# RS485Interface.net
KiCad netlist of a schematic drawn in EAGLE
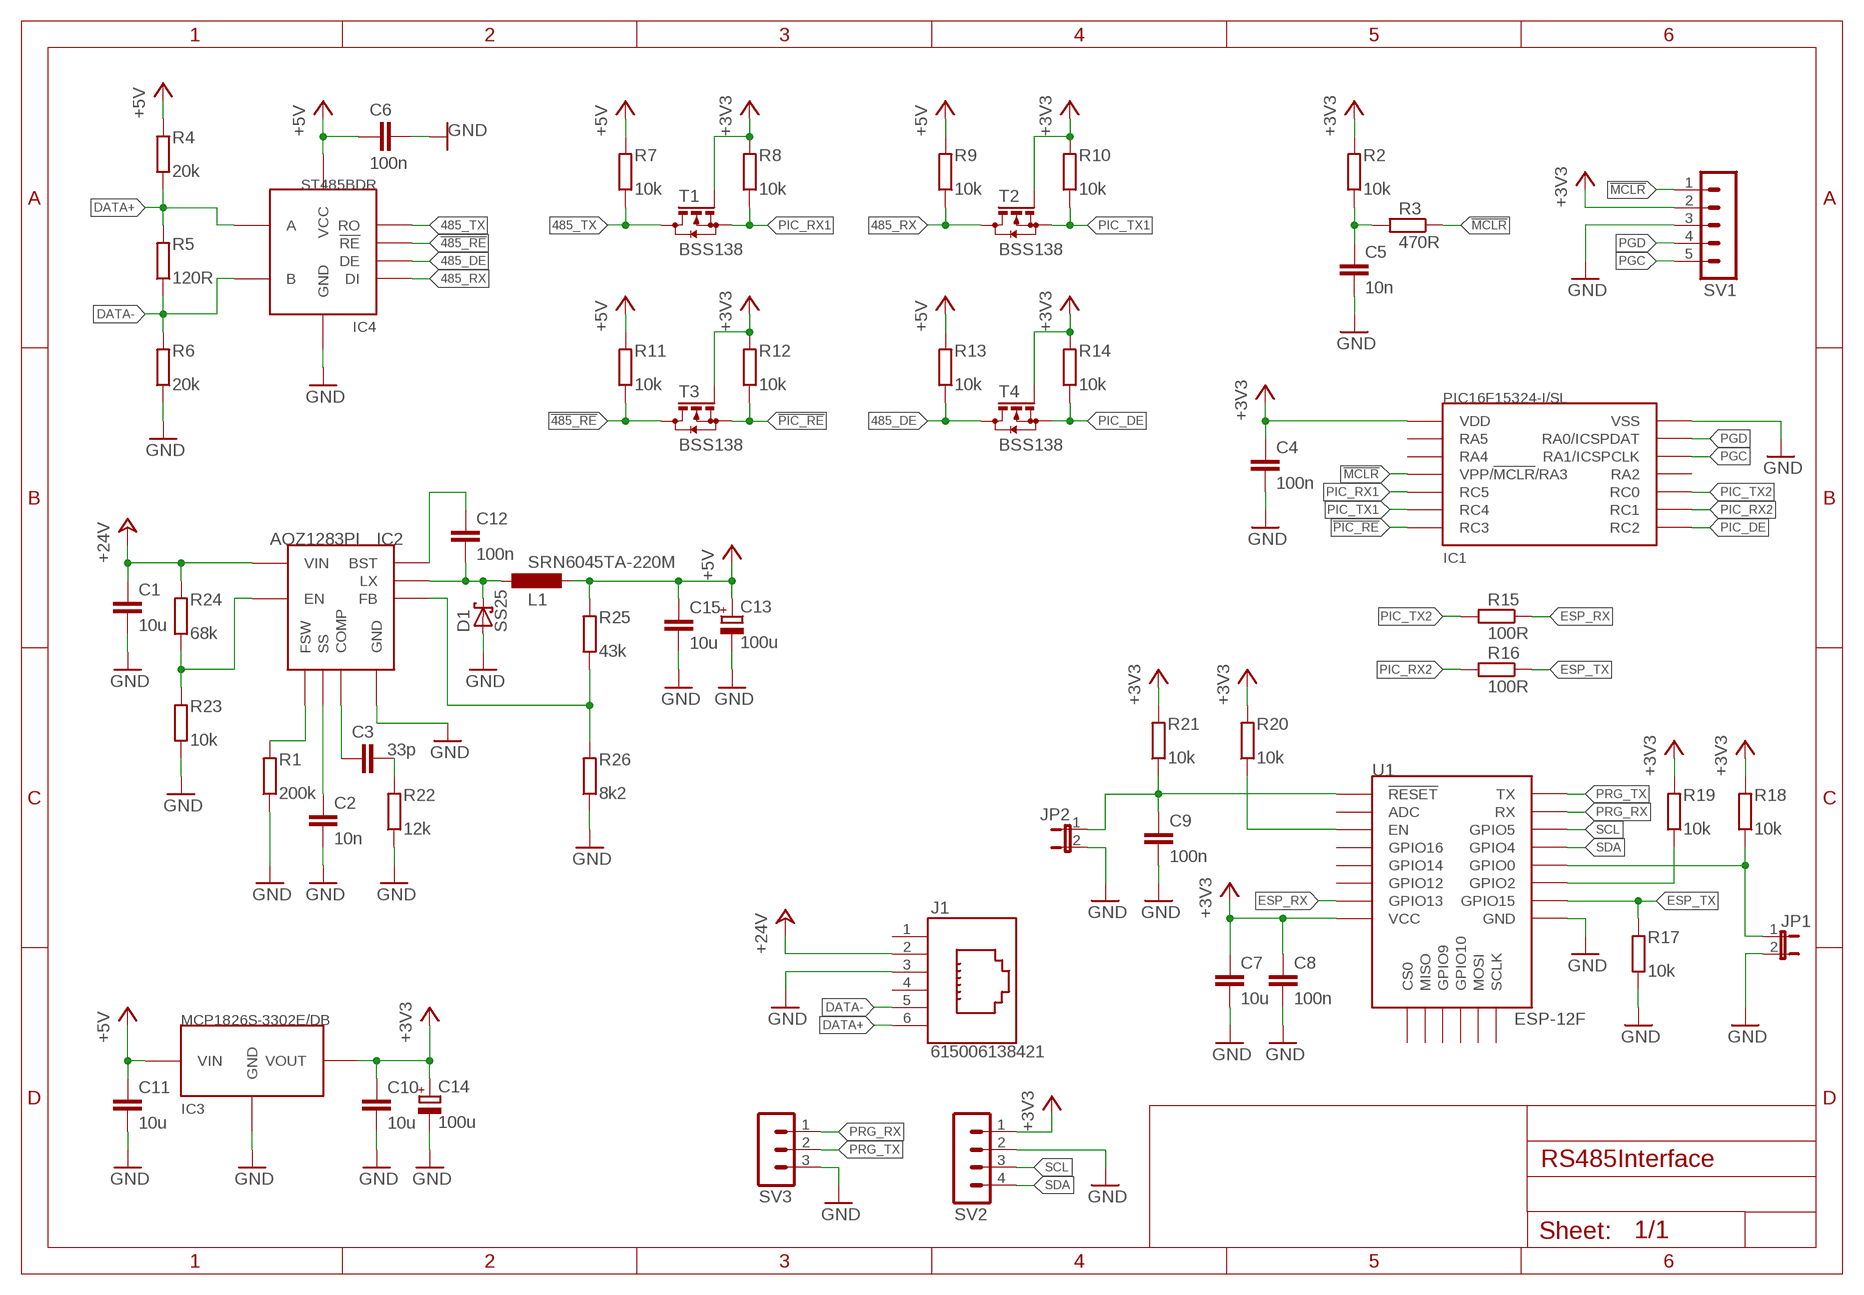
[diagram p0: schematic, sheet 1]

(export (version "E")
  (design (tool "Eeschema 10.0.6"))
  (components
    (comp (ref "C1")
      (value "10u")
      (footprint "eagle-import:C0805")
      (libsource (lib "eagle-import") (part "C-EUC0805"))
    )
    (comp (ref "C2")
      (value "10n")
      (footprint "eagle-import:C0805")
      (libsource (lib "eagle-import") (part "C-EUC0805"))
    )
    (comp (ref "C3")
      (value "33p")
      (footprint "eagle-import:C0805")
      (libsource (lib "eagle-import") (part "C-EUC0805"))
    )
    (comp (ref "C4")
      (value "100n")
      (footprint "eagle-import:C0805")
      (libsource (lib "eagle-import") (part "C-EUC0805"))
    )
    (comp (ref "C5")
      (value "10n")
      (footprint "eagle-import:C0805")
      (libsource (lib "eagle-import") (part "C-EUC0805"))
    )
    (comp (ref "C6")
      (value "100n")
      (footprint "eagle-import:C0805")
      (libsource (lib "eagle-import") (part "C-EUC0805"))
    )
    (comp (ref "C7")
      (value "10u")
      (footprint "eagle-import:C0805")
      (libsource (lib "eagle-import") (part "C-EUC0805"))
    )
    (comp (ref "C8")
      (value "100n")
      (footprint "eagle-import:C0805")
      (libsource (lib "eagle-import") (part "C-EUC0805"))
    )
    (comp (ref "C9")
      (value "100n")
      (footprint "eagle-import:C0805")
      (libsource (lib "eagle-import") (part "C-EUC0805"))
    )
    (comp (ref "C10")
      (value "10u")
      (footprint "eagle-import:C0805")
      (libsource (lib "eagle-import") (part "C-EUC0805"))
    )
    (comp (ref "C11")
      (value "10u")
      (footprint "eagle-import:C0805")
      (libsource (lib "eagle-import") (part "C-EUC0805"))
    )
    (comp (ref "C12")
      (value "100n")
      (footprint "eagle-import:C0805")
      (libsource (lib "eagle-import") (part "C-EUC0805"))
    )
    (comp (ref "C13")
      (value "100u")
      (footprint "eagle-import:UCL6.3")
      (libsource (lib "eagle-import") (part "UCL"))
    )
    (comp (ref "C14")
      (value "100u")
      (footprint "eagle-import:UCL6.3")
      (libsource (lib "eagle-import") (part "UCL"))
    )
    (comp (ref "C15")
      (value "10u")
      (footprint "eagle-import:C0805")
      (libsource (lib "eagle-import") (part "C-EUC0805"))
    )
    (comp (ref "D1")
      (value "SS25")
      (footprint "eagle-import:DO-214AA")
      (libsource (lib "eagle-import") (part "SS25"))
    )
    (comp (ref "IC1")
      (value "PIC16F15324-I/SL")
      (footprint "eagle-import:SOIC14")
      (libsource (lib "eagle-import") (part "PIC16F15324-I/SL"))
    )
    (comp (ref "IC2")
      (value "AOZ1283PI")
      (footprint "eagle-import:SO8+PAD")
      (libsource (lib "eagle-import") (part "AOZ1283PI"))
    )
    (comp (ref "IC3")
      (value "MCP1826S-3302E/DB")
      (footprint "eagle-import:SOT-223-3")
      (libsource (lib "eagle-import") (part "MCP1826S-3302E/DB"))
    )
    (comp (ref "IC4")
      (value "ST485BDR")
      (footprint "eagle-import:SOIC8")
      (libsource (lib "eagle-import") (part "ST485BDR"))
    )
    (comp (ref "J1")
      (value "615006138421")
      (footprint "eagle-import:615006138421")
      (libsource (lib "eagle-import") (part "615006138421"))
    )
    (comp (ref "JP1")
      (value "JP1E")
      (footprint "eagle-import:JP1")
      (libsource (lib "eagle-import") (part "JP1E"))
    )
    (comp (ref "JP2")
      (value "JP1E")
      (footprint "eagle-import:JP1")
      (libsource (lib "eagle-import") (part "JP1E"))
    )
    (comp (ref "L1")
      (value "SRN6045TA-220M")
      (footprint "eagle-import:SRN6045TA")
      (libsource (lib "eagle-import") (part "SRN6045TA-220M"))
    )
    (comp (ref "R1")
      (value "200k")
      (footprint "eagle-import:R0805")
      (libsource (lib "eagle-import") (part "R-EU_R0805"))
    )
    (comp (ref "R2")
      (value "10k")
      (footprint "eagle-import:R0805")
      (libsource (lib "eagle-import") (part "R-EU_R0805"))
    )
    (comp (ref "R3")
      (value "470R")
      (footprint "eagle-import:R0805")
      (libsource (lib "eagle-import") (part "R-EU_R0805"))
    )
    (comp (ref "R4")
      (value "20k")
      (footprint "eagle-import:R0805")
      (libsource (lib "eagle-import") (part "R-EU_R0805"))
    )
    (comp (ref "R5")
      (value "120R")
      (footprint "eagle-import:R0805")
      (libsource (lib "eagle-import") (part "R-EU_R0805"))
    )
    (comp (ref "R6")
      (value "20k")
      (footprint "eagle-import:R0805")
      (libsource (lib "eagle-import") (part "R-EU_R0805"))
    )
    (comp (ref "R7")
      (value "10k")
      (footprint "eagle-import:R0805")
      (libsource (lib "eagle-import") (part "R-EU_R0805"))
    )
    (comp (ref "R8")
      (value "10k")
      (footprint "eagle-import:R0805")
      (libsource (lib "eagle-import") (part "R-EU_R0805"))
    )
    (comp (ref "R9")
      (value "10k")
      (footprint "eagle-import:R0805")
      (libsource (lib "eagle-import") (part "R-EU_R0805"))
    )
    (comp (ref "R10")
      (value "10k")
      (footprint "eagle-import:R0805")
      (libsource (lib "eagle-import") (part "R-EU_R0805"))
    )
    (comp (ref "R11")
      (value "10k")
      (footprint "eagle-import:R0805")
      (libsource (lib "eagle-import") (part "R-EU_R0805"))
    )
    (comp (ref "R12")
      (value "10k")
      (footprint "eagle-import:R0805")
      (libsource (lib "eagle-import") (part "R-EU_R0805"))
    )
    (comp (ref "R13")
      (value "10k")
      (footprint "eagle-import:R0805")
      (libsource (lib "eagle-import") (part "R-EU_R0805"))
    )
    (comp (ref "R14")
      (value "10k")
      (footprint "eagle-import:R0805")
      (libsource (lib "eagle-import") (part "R-EU_R0805"))
    )
    (comp (ref "R15")
      (value "100R")
      (footprint "eagle-import:R0805")
      (libsource (lib "eagle-import") (part "R-EU_R0805"))
    )
    (comp (ref "R16")
      (value "100R")
      (footprint "eagle-import:R0805")
      (libsource (lib "eagle-import") (part "R-EU_R0805"))
    )
    (comp (ref "R17")
      (value "10k")
      (footprint "eagle-import:R0805")
      (libsource (lib "eagle-import") (part "R-EU_R0805"))
    )
    (comp (ref "R18")
      (value "10k")
      (footprint "eagle-import:R0805")
      (libsource (lib "eagle-import") (part "R-EU_R0805"))
    )
    (comp (ref "R19")
      (value "10k")
      (footprint "eagle-import:R0805")
      (libsource (lib "eagle-import") (part "R-EU_R0805"))
    )
    (comp (ref "R20")
      (value "10k")
      (footprint "eagle-import:R0805")
      (libsource (lib "eagle-import") (part "R-EU_R0805"))
    )
    (comp (ref "R21")
      (value "10k")
      (footprint "eagle-import:R0805")
      (libsource (lib "eagle-import") (part "R-EU_R0805"))
    )
    (comp (ref "R22")
      (value "12k")
      (footprint "eagle-import:R0805")
      (libsource (lib "eagle-import") (part "R-EU_R0805"))
    )
    (comp (ref "R23")
      (value "10k")
      (footprint "eagle-import:R0805")
      (libsource (lib "eagle-import") (part "R-EU_R0805"))
    )
    (comp (ref "R24")
      (value "68k")
      (footprint "eagle-import:R0805")
      (libsource (lib "eagle-import") (part "R-EU_R0805"))
    )
    (comp (ref "R25")
      (value "43k")
      (footprint "eagle-import:R0805")
      (libsource (lib "eagle-import") (part "R-EU_R0805"))
    )
    (comp (ref "R26")
      (value "8k2")
      (footprint "eagle-import:R0805")
      (libsource (lib "eagle-import") (part "R-EU_R0805"))
    )
    (comp (ref "SV1")
      (value "MA05-1")
      (footprint "eagle-import:MA05-1")
      (libsource (lib "eagle-import") (part "MA05-1"))
    )
    (comp (ref "SV2")
      (value "MA04-1")
      (footprint "eagle-import:MA04-1")
      (libsource (lib "eagle-import") (part "MA04-1"))
    )
    (comp (ref "SV3")
      (value "MA03-1")
      (footprint "eagle-import:MA03-1")
      (libsource (lib "eagle-import") (part "MA03-1"))
    )
    (comp (ref "T1")
      (value "BSS138")
      (footprint "eagle-import:SOT-23")
      (libsource (lib "eagle-import") (part "BSS138"))
    )
    (comp (ref "T2")
      (value "BSS138")
      (footprint "eagle-import:SOT-23")
      (libsource (lib "eagle-import") (part "BSS138"))
    )
    (comp (ref "T3")
      (value "BSS138")
      (footprint "eagle-import:SOT-23")
      (libsource (lib "eagle-import") (part "BSS138"))
    )
    (comp (ref "T4")
      (value "BSS138")
      (footprint "eagle-import:SOT-23")
      (libsource (lib "eagle-import") (part "BSS138"))
    )
    (comp (ref "U1")
      (value "ESP-12F")
      (footprint "eagle-import:ESP12E-SMD")
      (libsource (lib "eagle-import") (part "ESP12ESMD"))
    )
  )
  (nets
    (net (code "1") (name "+3V3") (class "Default")
      (node (ref "C10") (pin "1") (pinfunction "1_1") (pintype "passive"))
      (node (ref "C14") (pin "+") (pinfunction "+_+") (pintype "passive"))
      (node (ref "C4") (pin "1") (pinfunction "1_1") (pintype "passive"))
      (node (ref "C7") (pin "1") (pinfunction "1_1") (pintype "passive"))
      (node (ref "C8") (pin "1") (pinfunction "1_1") (pintype "passive"))
      (node (ref "IC1") (pin "P1") (pinfunction "VDD_P1") (pintype "power_in"))
      (node (ref "IC3") (pin "P3") (pinfunction "VOUT_P3") (pintype "power_in"))
      (node (ref "R10") (pin "2") (pinfunction "2_2") (pintype "passive"))
      (node (ref "R12") (pin "2") (pinfunction "2_2") (pintype "passive"))
      (node (ref "R14") (pin "2") (pinfunction "2_2") (pintype "passive"))
      (node (ref "R18") (pin "2") (pinfunction "2_2") (pintype "passive"))
      (node (ref "R19") (pin "2") (pinfunction "2_2") (pintype "passive"))
      (node (ref "R2") (pin "2") (pinfunction "2_2") (pintype "passive"))
      (node (ref "R20") (pin "2") (pinfunction "2_2") (pintype "passive"))
      (node (ref "R21") (pin "2") (pinfunction "2_2") (pintype "passive"))
      (node (ref "R8") (pin "2") (pinfunction "2_2") (pintype "passive"))
      (node (ref "SV1") (pin "2") (pinfunction "2_2") (pintype "passive"))
      (node (ref "SV2") (pin "1") (pinfunction "1_1") (pintype "passive"))
      (node (ref "T1") (pin "P1") (pinfunction "G_P1") (pintype "passive"))
      (node (ref "T2") (pin "P1") (pinfunction "G_P1") (pintype "passive"))
      (node (ref "T3") (pin "P1") (pinfunction "G_P1") (pintype "passive"))
      (node (ref "T4") (pin "P1") (pinfunction "G_P1") (pintype "passive"))
      (node (ref "U1") (pin "VCC") (pinfunction "VCC_VCC") (pintype "bidirectional"))
    )
    (net (code "2") (name "+5V") (class "Default")
      (node (ref "C11") (pin "1") (pinfunction "1_1") (pintype "passive"))
      (node (ref "C13") (pin "+") (pinfunction "+_+") (pintype "passive"))
      (node (ref "C15") (pin "1") (pinfunction "1_1") (pintype "passive"))
      (node (ref "C6") (pin "1") (pinfunction "1_1") (pintype "passive"))
      (node (ref "IC3") (pin "P1") (pinfunction "VIN_P1") (pintype "power_in"))
      (node (ref "IC4") (pin "P8") (pinfunction "VCC_P8") (pintype "power_in"))
      (node (ref "L1") (pin "P$1") (pinfunction "1_P$1") (pintype "passive"))
      (node (ref "R11") (pin "2") (pinfunction "2_2") (pintype "passive"))
      (node (ref "R13") (pin "2") (pinfunction "2_2") (pintype "passive"))
      (node (ref "R25") (pin "2") (pinfunction "2_2") (pintype "passive"))
      (node (ref "R4") (pin "2") (pinfunction "2_2") (pintype "passive"))
      (node (ref "R7") (pin "2") (pinfunction "2_2") (pintype "passive"))
      (node (ref "R9") (pin "2") (pinfunction "2_2") (pintype "passive"))
    )
    (net (code "3") (name "+24V") (class "Default")
      (node (ref "C1") (pin "1") (pinfunction "1_1") (pintype "passive"))
      (node (ref "IC2") (pin "PAD") (pinfunction "VIN_PAD") (pintype "power_in"))
      (node (ref "J1") (pin "2") (pinfunction "5_2") (pintype "passive"))
      (node (ref "R24") (pin "2") (pinfunction "2_2") (pintype "passive"))
    )
    (net (code "4") (name "/~{485_RE}") (class "Default")
      (node (ref "IC4") (pin "P2") (pinfunction "~{RE}_P2") (pintype "bidirectional"))
      (node (ref "R11") (pin "1") (pinfunction "1_1") (pintype "passive"))
      (node (ref "T3") (pin "P3") (pinfunction "D_P3") (pintype "passive"))
    )
    (net (code "5") (name "/~{MCLR}") (class "Default")
      (node (ref "IC1") (pin "P4") (pinfunction "VPP/~{MCLR}/RA3_P4") (pintype "bidirectional"))
      (node (ref "R3") (pin "1") (pinfunction "1_1") (pintype "passive"))
      (node (ref "SV1") (pin "1") (pinfunction "1_1") (pintype "passive"))
    )
    (net (code "6") (name "/~{PIC_RE}") (class "Default")
      (node (ref "IC1") (pin "P7") (pinfunction "RC3_P7") (pintype "bidirectional"))
      (node (ref "R12") (pin "1") (pinfunction "1_1") (pintype "passive"))
      (node (ref "T3") (pin "P2") (pinfunction "S_P2") (pintype "passive"))
    )
    (net (code "7") (name "485_DE") (class "Default")
      (node (ref "IC4") (pin "P3") (pinfunction "DE_P3") (pintype "bidirectional"))
      (node (ref "R13") (pin "1") (pinfunction "1_1") (pintype "passive"))
      (node (ref "T4") (pin "P3") (pinfunction "D_P3") (pintype "passive"))
    )
    (net (code "8") (name "485_RX") (class "Default")
      (node (ref "IC4") (pin "P4") (pinfunction "DI_P4") (pintype "bidirectional"))
      (node (ref "R9") (pin "1") (pinfunction "1_1") (pintype "passive"))
      (node (ref "T2") (pin "P3") (pinfunction "D_P3") (pintype "passive"))
    )
    (net (code "9") (name "485_TX") (class "Default")
      (node (ref "IC4") (pin "P1") (pinfunction "RO_P1") (pintype "bidirectional"))
      (node (ref "R7") (pin "1") (pinfunction "1_1") (pintype "passive"))
      (node (ref "T1") (pin "P3") (pinfunction "D_P3") (pintype "passive"))
    )
    (net (code "10") (name "DATA+") (class "Default")
      (node (ref "IC4") (pin "P6") (pinfunction "A_P6") (pintype "bidirectional"))
      (node (ref "J1") (pin "6") (pinfunction "1_6") (pintype "passive"))
      (node (ref "R4") (pin "1") (pinfunction "1_1") (pintype "passive"))
      (node (ref "R5") (pin "2") (pinfunction "2_2") (pintype "passive"))
    )
    (net (code "11") (name "DATA-") (class "Default")
      (node (ref "IC4") (pin "P7") (pinfunction "B_P7") (pintype "bidirectional"))
      (node (ref "J1") (pin "5") (pinfunction "2_5") (pintype "passive"))
      (node (ref "R5") (pin "1") (pinfunction "1_1") (pintype "passive"))
      (node (ref "R6") (pin "2") (pinfunction "2_2") (pintype "passive"))
    )
    (net (code "12") (name "ESP_RX") (class "Default")
      (node (ref "R15") (pin "1") (pinfunction "1_1") (pintype "passive"))
      (node (ref "U1") (pin "GPIO13") (pinfunction "GPIO13_GPIO13") (pintype "bidirectional"))
    )
    (net (code "13") (name "ESP_TX") (class "Default")
      (node (ref "R16") (pin "1") (pinfunction "1_1") (pintype "passive"))
      (node (ref "R17") (pin "2") (pinfunction "2_2") (pintype "passive"))
      (node (ref "U1") (pin "GPIO15") (pinfunction "GPIO15_GPIO15") (pintype "bidirectional"))
    )
    (net (code "14") (name "GND") (class "Default")
      (node (ref "C1") (pin "2") (pinfunction "2_2") (pintype "passive"))
      (node (ref "C10") (pin "2") (pinfunction "2_2") (pintype "passive"))
      (node (ref "C11") (pin "2") (pinfunction "2_2") (pintype "passive"))
      (node (ref "C13") (pin "-") (pinfunction "-_-") (pintype "passive"))
      (node (ref "C14") (pin "-") (pinfunction "-_-") (pintype "passive"))
      (node (ref "C15") (pin "2") (pinfunction "2_2") (pintype "passive"))
      (node (ref "C2") (pin "2") (pinfunction "2_2") (pintype "passive"))
      (node (ref "C4") (pin "2") (pinfunction "2_2") (pintype "passive"))
      (node (ref "C5") (pin "2") (pinfunction "2_2") (pintype "passive"))
      (node (ref "C6") (pin "2") (pinfunction "2_2") (pintype "passive"))
      (node (ref "C7") (pin "2") (pinfunction "2_2") (pintype "passive"))
      (node (ref "C8") (pin "2") (pinfunction "2_2") (pintype "passive"))
      (node (ref "C9") (pin "2") (pinfunction "2_2") (pintype "passive"))
      (node (ref "D1") (pin "A") (pinfunction "A_A") (pintype "passive"))
      (node (ref "IC1") (pin "P14") (pinfunction "VSS_P14") (pintype "power_in"))
      (node (ref "IC2") (pin "P3") (pinfunction "GND_P3") (pintype "power_in"))
      (node (ref "IC3") (pin "P2") (pinfunction "GND_P2") (pintype "power_in"))
      (node (ref "IC3") (pin "P4") (pinfunction "GND_P4") (pintype "power_in"))
      (node (ref "IC4") (pin "P5") (pinfunction "GND_P5") (pintype "power_in"))
      (node (ref "J1") (pin "3") (pinfunction "4_3") (pintype "passive"))
      (node (ref "JP1") (pin "2") (pinfunction "2_2") (pintype "passive"))
      (node (ref "JP2") (pin "2") (pinfunction "2_2") (pintype "passive"))
      (node (ref "R1") (pin "1") (pinfunction "1_1") (pintype "passive"))
      (node (ref "R17") (pin "1") (pinfunction "1_1") (pintype "passive"))
      (node (ref "R22") (pin "1") (pinfunction "1_1") (pintype "passive"))
      (node (ref "R23") (pin "1") (pinfunction "1_1") (pintype "passive"))
      (node (ref "R26") (pin "1") (pinfunction "1_1") (pintype "passive"))
      (node (ref "R6") (pin "1") (pinfunction "1_1") (pintype "passive"))
      (node (ref "SV1") (pin "3") (pinfunction "3_3") (pintype "passive"))
      (node (ref "SV2") (pin "2") (pinfunction "2_2") (pintype "passive"))
      (node (ref "SV3") (pin "3") (pinfunction "3_3") (pintype "passive"))
      (node (ref "U1") (pin "GND") (pinfunction "GND_GND") (pintype "bidirectional"))
    )
    (net (code "15") (name "Net-(C3-Pad2)") (class "Default")
      (node (ref "C3") (pin "2") (pinfunction "2_2") (pintype "passive"))
      (node (ref "R22") (pin "2") (pinfunction "2_2") (pintype "passive"))
    )
    (net (code "16") (name "Net-(C5-Pad1)") (class "Default")
      (node (ref "C5") (pin "1") (pinfunction "1_1") (pintype "passive"))
      (node (ref "R2") (pin "1") (pinfunction "1_1") (pintype "passive"))
      (node (ref "R3") (pin "2") (pinfunction "2_2") (pintype "passive"))
    )
    (net (code "17") (name "Net-(IC2-BST)") (class "Default")
      (node (ref "C12") (pin "1") (pinfunction "1_1") (pintype "passive"))
      (node (ref "IC2") (pin "P2") (pinfunction "BST_P2") (pintype "power_in"))
    )
    (net (code "18") (name "Net-(IC2-COMP)") (class "Default")
      (node (ref "C3") (pin "1") (pinfunction "1_1") (pintype "passive"))
      (node (ref "IC2") (pin "P5") (pinfunction "COMP_P5") (pintype "bidirectional"))
    )
    (net (code "19") (name "Net-(IC2-EN)") (class "Default")
      (node (ref "IC2") (pin "P8") (pinfunction "EN_P8") (pintype "bidirectional"))
      (node (ref "R23") (pin "2") (pinfunction "2_2") (pintype "passive"))
      (node (ref "R24") (pin "1") (pinfunction "1_1") (pintype "passive"))
    )
    (net (code "20") (name "Net-(IC2-FB)") (class "Default")
      (node (ref "IC2") (pin "P6") (pinfunction "FB_P6") (pintype "bidirectional"))
      (node (ref "R25") (pin "1") (pinfunction "1_1") (pintype "passive"))
      (node (ref "R26") (pin "2") (pinfunction "2_2") (pintype "passive"))
    )
    (net (code "21") (name "Net-(IC2-FSW)") (class "Default")
      (node (ref "IC2") (pin "P4") (pinfunction "FSW_P4") (pintype "bidirectional"))
      (node (ref "R1") (pin "2") (pinfunction "2_2") (pintype "passive"))
    )
    (net (code "22") (name "Net-(IC2-LX)") (class "Default")
      (node (ref "C12") (pin "2") (pinfunction "2_2") (pintype "passive"))
      (node (ref "D1") (pin "C") (pinfunction "C_C") (pintype "passive"))
      (node (ref "IC2") (pin "P1") (pinfunction "LX_P1") (pintype "power_in"))
      (node (ref "L1") (pin "P$2") (pinfunction "2_P$2") (pintype "passive"))
    )
    (net (code "23") (name "Net-(IC2-SS)") (class "Default")
      (node (ref "C2") (pin "1") (pinfunction "1_1") (pintype "passive"))
      (node (ref "IC2") (pin "P7") (pinfunction "SS_P7") (pintype "bidirectional"))
    )
    (net (code "24") (name "Net-(JP1-Pad1)") (class "Default")
      (node (ref "JP1") (pin "1") (pinfunction "1_1") (pintype "passive"))
      (node (ref "R18") (pin "1") (pinfunction "1_1") (pintype "passive"))
      (node (ref "U1") (pin "GPIO0") (pinfunction "GPIO0_GPIO0") (pintype "bidirectional"))
    )
    (net (code "25") (name "Net-(R19-Pad1)") (class "Default")
      (node (ref "R19") (pin "1") (pinfunction "1_1") (pintype "passive"))
      (node (ref "U1") (pin "GPIO2") (pinfunction "GPIO2_GPIO2") (pintype "bidirectional"))
    )
    (net (code "26") (name "Net-(R20-Pad1)") (class "Default")
      (node (ref "R20") (pin "1") (pinfunction "1_1") (pintype "passive"))
      (node (ref "U1") (pin "EN") (pinfunction "EN_EN") (pintype "bidirectional"))
    )
    (net (code "27") (name "Net-(U1-~{RESET})") (class "Default")
      (node (ref "C9") (pin "1") (pinfunction "1_1") (pintype "passive"))
      (node (ref "JP2") (pin "1") (pinfunction "1_1") (pintype "passive"))
      (node (ref "R21") (pin "1") (pinfunction "1_1") (pintype "passive"))
      (node (ref "U1") (pin "RESET") (pinfunction "~{RESET}_RESET") (pintype "bidirectional"))
    )
    (net (code "28") (name "PGC") (class "Default")
      (node (ref "IC1") (pin "P12") (pinfunction "RA1/ICSPCLK_P12") (pintype "bidirectional"))
      (node (ref "SV1") (pin "5") (pinfunction "5_5") (pintype "passive"))
    )
    (net (code "29") (name "PGD") (class "Default")
      (node (ref "IC1") (pin "P13") (pinfunction "RA0/ICSPDAT_P13") (pintype "bidirectional"))
      (node (ref "SV1") (pin "4") (pinfunction "4_4") (pintype "passive"))
    )
    (net (code "30") (name "PIC_DE") (class "Default")
      (node (ref "IC1") (pin "P8") (pinfunction "RC2_P8") (pintype "bidirectional"))
      (node (ref "R14") (pin "1") (pinfunction "1_1") (pintype "passive"))
      (node (ref "T4") (pin "P2") (pinfunction "S_P2") (pintype "passive"))
    )
    (net (code "31") (name "PIC_RX1") (class "Default")
      (node (ref "IC1") (pin "P5") (pinfunction "RC5_P5") (pintype "bidirectional"))
      (node (ref "R8") (pin "1") (pinfunction "1_1") (pintype "passive"))
      (node (ref "T1") (pin "P2") (pinfunction "S_P2") (pintype "passive"))
    )
    (net (code "32") (name "PIC_RX2") (class "Default")
      (node (ref "IC1") (pin "P9") (pinfunction "RC1_P9") (pintype "bidirectional"))
      (node (ref "R16") (pin "2") (pinfunction "2_2") (pintype "passive"))
    )
    (net (code "33") (name "PIC_TX1") (class "Default")
      (node (ref "IC1") (pin "P6") (pinfunction "RC4_P6") (pintype "bidirectional"))
      (node (ref "R10") (pin "1") (pinfunction "1_1") (pintype "passive"))
      (node (ref "T2") (pin "P2") (pinfunction "S_P2") (pintype "passive"))
    )
    (net (code "34") (name "PIC_TX2") (class "Default")
      (node (ref "IC1") (pin "P10") (pinfunction "RC0_P10") (pintype "bidirectional"))
      (node (ref "R15") (pin "2") (pinfunction "2_2") (pintype "passive"))
    )
    (net (code "35") (name "PRG_RX") (class "Default")
      (node (ref "SV3") (pin "1") (pinfunction "1_1") (pintype "passive"))
      (node (ref "U1") (pin "RXD0") (pinfunction "RX_RXD0") (pintype "bidirectional"))
    )
    (net (code "36") (name "PRG_TX") (class "Default")
      (node (ref "SV3") (pin "2") (pinfunction "2_2") (pintype "passive"))
      (node (ref "U1") (pin "TXD0") (pinfunction "TX_TXD0") (pintype "bidirectional"))
    )
    (net (code "37") (name "SCL") (class "Default")
      (node (ref "SV2") (pin "3") (pinfunction "3_3") (pintype "passive"))
      (node (ref "U1") (pin "GPIO5") (pinfunction "GPIO5_GPIO5") (pintype "bidirectional"))
    )
    (net (code "38") (name "SDA") (class "Default")
      (node (ref "SV2") (pin "4") (pinfunction "4_4") (pintype "passive"))
      (node (ref "U1") (pin "GPIO4") (pinfunction "GPIO4_GPIO4") (pintype "bidirectional"))
    )
    (net (code "39") (name "unconnected-(IC1-RA2-PadP11)") (class "Default")
      (node (ref "IC1") (pin "P11") (pinfunction "RA2_P11") (pintype "bidirectional"))
    )
    (net (code "40") (name "unconnected-(IC1-RA4-PadP3)") (class "Default")
      (node (ref "IC1") (pin "P3") (pinfunction "RA4_P3") (pintype "bidirectional"))
    )
    (net (code "41") (name "unconnected-(IC1-RA5-PadP2)") (class "Default")
      (node (ref "IC1") (pin "P2") (pinfunction "RA5_P2") (pintype "bidirectional"))
    )
    (net (code "42") (name "unconnected-(J1-3-Pad4)") (class "Default")
      (node (ref "J1") (pin "4") (pinfunction "3_4") (pintype "passive"))
    )
    (net (code "43") (name "unconnected-(J1-6-Pad1)") (class "Default")
      (node (ref "J1") (pin "1") (pinfunction "6_1") (pintype "passive"))
    )
    (net (code "44") (name "unconnected-(U1-PadADC)") (class "Default")
      (node (ref "U1") (pin "ADC") (pinfunction "ADC_ADC") (pintype "bidirectional"))
    )
    (net (code "45") (name "unconnected-(U1-PadCS0)") (class "Default")
      (node (ref "U1") (pin "CS0") (pinfunction "CS0_CS0") (pintype "bidirectional"))
    )
    (net (code "46") (name "unconnected-(U1-PadGPIO9)") (class "Default")
      (node (ref "U1") (pin "GPIO9") (pinfunction "GPIO9_GPIO9") (pintype "bidirectional"))
    )
    (net (code "47") (name "unconnected-(U1-PadGPIO10)") (class "Default")
      (node (ref "U1") (pin "GPIO10") (pinfunction "GPIO10_GPIO10") (pintype "bidirectional"))
    )
    (net (code "48") (name "unconnected-(U1-PadGPIO12)") (class "Default")
      (node (ref "U1") (pin "GPIO12") (pinfunction "GPIO12_GPIO12") (pintype "bidirectional"))
    )
    (net (code "49") (name "unconnected-(U1-PadGPIO14)") (class "Default")
      (node (ref "U1") (pin "GPIO14") (pinfunction "GPIO14_GPIO14") (pintype "bidirectional"))
    )
    (net (code "50") (name "unconnected-(U1-PadGPIO16)") (class "Default")
      (node (ref "U1") (pin "GPIO16") (pinfunction "GPIO16_GPIO16") (pintype "bidirectional"))
    )
    (net (code "51") (name "unconnected-(U1-PadMISO)") (class "Default")
      (node (ref "U1") (pin "MISO") (pinfunction "MISO_MISO") (pintype "bidirectional"))
    )
    (net (code "52") (name "unconnected-(U1-PadMOSI)") (class "Default")
      (node (ref "U1") (pin "MOSI") (pinfunction "MOSI_MOSI") (pintype "bidirectional"))
    )
    (net (code "53") (name "unconnected-(U1-PadSCLK)") (class "Default")
      (node (ref "U1") (pin "SCLK") (pinfunction "SCLK_SCLK") (pintype "bidirectional"))
    )
  )
)
